# BQ_Chip.net
KiCad netlist of a schematic drawn in Altium Designer
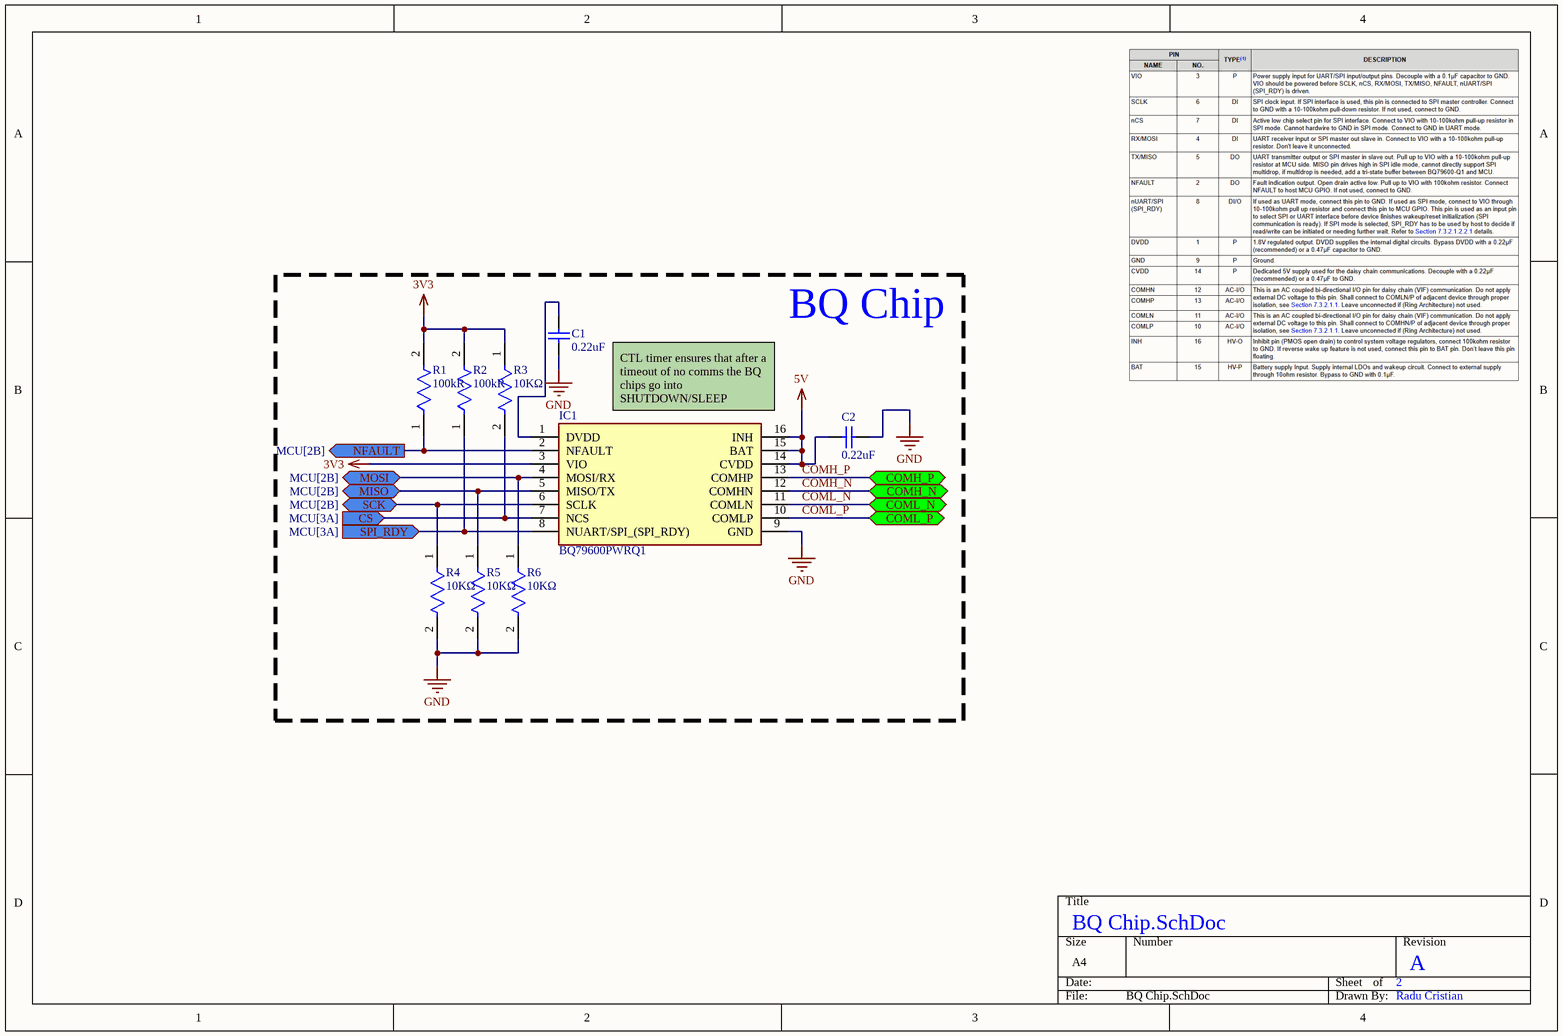
[diagram p0: BQ Chip.SchDoc]

(export (version "E")
  (design (tool "Eeschema 10.0.6"))
  (components
    (comp (ref "C1")
      (value "VJ0603Y224KXXCW1BC")
      (footprint "CAPC1608X95X40ML15T15")
      (fields (field (name "MANUFACTURER") "Vitramon") (field (name "PARAMETER 1") "0.22uF"))
      (libsource (lib "Altium Content Vault") (part "CAP"))
    )
    (comp (ref "C2")
      (value "VJ0603Y224KXXCW1BC")
      (footprint "CAPC1608X95X40ML15T15")
      (fields (field (name "MANUFACTURER") "Vitramon") (field (name "PARAMETER 1") "0.22uF"))
      (libsource (lib "Altium Content Vault") (part "CAP"))
    )
    (comp (ref "IC1")
      (value "BQ79600PWRQ1")
      (footprint "SamacSys:SOP65P640X120-16N")
      (description "Integrated Circuit")
      (fields (field (name "MOUSER PART NUMBER") "595-BQ79600PWRQ1"))
      (libsource (lib "*") (part "BQ79600PWRQ1"))
    )
    (comp (ref "R1")
      (value "MCT0603MC1003FP500")
      (footprint "FP-MCT0603-IPC_C")
      (description "RES SMD 100 OHM 1% 1/8W 0603")
      (fields (field (name "TOLERANCE") "1%") (field (name "RESISTANCE") "100kR"))
      (libsource (lib "Altium Content Vault") (part "1029c3af85768c4190bb7ad29bc67b5"))
    )
    (comp (ref "R2")
      (value "MCT0603MC1003FP500")
      (footprint "FP-MCT0603-IPC_C")
      (description "RES SMD 100 OHM 1% 1/8W 0603")
      (fields (field (name "TOLERANCE") "1%") (field (name "RESISTANCE") "100kR"))
      (libsource (lib "Altium Content Vault") (part "1029c3af85768c4190bb7ad29bc67b5"))
    )
    (comp (ref "R3")
      (value "CRGP0603F10K")
      (footprint "FP-CRGP0603-IPC_C")
      (description "CRGP 0603 10K 1%")
      (fields
        (field (name "OCTOPART") "https://octopart.com/crgp0603f10k-te+connectivity-91018721")
        (field (name "TOLERANCE") "0.01")
        (field (name "RESISTANCE") "10KΩ")
      )
      (libsource (lib "Altium Content Vault") (part "1029c3af85768c4190bb7ad29bc67b5"))
    )
    (comp (ref "R4")
      (value "CRGP0603F10K")
      (footprint "FP-CRGP0603-IPC_C")
      (description "CRGP 0603 10K 1%")
      (fields
        (field (name "OCTOPART") "https://octopart.com/crgp0603f10k-te+connectivity-91018721")
        (field (name "TOLERANCE") "0.01")
        (field (name "RESISTANCE") "10KΩ")
      )
      (libsource (lib "Altium Content Vault") (part "1029c3af85768c4190bb7ad29bc67b5"))
    )
    (comp (ref "R5")
      (value "CRGP0603F10K")
      (footprint "FP-CRGP0603-IPC_C")
      (description "CRGP 0603 10K 1%")
      (fields
        (field (name "OCTOPART") "https://octopart.com/crgp0603f10k-te+connectivity-91018721")
        (field (name "TOLERANCE") "0.01")
        (field (name "RESISTANCE") "10KΩ")
      )
      (libsource (lib "Altium Content Vault") (part "1029c3af85768c4190bb7ad29bc67b5"))
    )
    (comp (ref "R6")
      (value "CRGP0603F10K")
      (footprint "FP-CRGP0603-IPC_C")
      (description "CRGP 0603 10K 1%")
      (fields
        (field (name "OCTOPART") "https://octopart.com/crgp0603f10k-te+connectivity-91018721")
        (field (name "TOLERANCE") "0.01")
        (field (name "RESISTANCE") "10KΩ")
      )
      (libsource (lib "Altium Content Vault") (part "1029c3af85768c4190bb7ad29bc67b5"))
    )
  )
  (nets
    (net (code "1") (name "/COMH_N") (class "Default")
      (node (ref "IC1") (pin "12") (pinfunction "COMHN_12") (pintype "passive"))
    )
    (net (code "2") (name "/COMH_P") (class "Default")
      (node (ref "IC1") (pin "13") (pinfunction "COMHP_13") (pintype "passive"))
    )
    (net (code "3") (name "/COML_N") (class "Default")
      (node (ref "IC1") (pin "11") (pinfunction "COMLN_11") (pintype "passive"))
    )
    (net (code "4") (name "/COML_P") (class "Default")
      (node (ref "IC1") (pin "10") (pinfunction "COMLP_10") (pintype "passive"))
    )
    (net (code "5") (name "/CS") (class "Default")
      (node (ref "IC1") (pin "7") (pinfunction "NCS_7") (pintype "passive"))
      (node (ref "R3") (pin "2") (pinfunction "2_2") (pintype "passive"))
    )
    (net (code "6") (name "/MISO") (class "Default")
      (node (ref "IC1") (pin "5") (pinfunction "MISO/TX_5") (pintype "passive"))
      (node (ref "R5") (pin "1") (pinfunction "1_1") (pintype "passive"))
    )
    (net (code "7") (name "/MOSI") (class "Default")
      (node (ref "IC1") (pin "4") (pinfunction "MOSI/RX_4") (pintype "passive"))
      (node (ref "R6") (pin "1") (pinfunction "1_1") (pintype "passive"))
    )
    (net (code "8") (name "/NFAULT") (class "Default")
      (node (ref "IC1") (pin "2") (pinfunction "NFAULT_2") (pintype "passive"))
      (node (ref "R1") (pin "1") (pinfunction "1_1") (pintype "passive"))
    )
    (net (code "9") (name "/SCK") (class "Default")
      (node (ref "IC1") (pin "6") (pinfunction "SCLK_6") (pintype "passive"))
      (node (ref "R4") (pin "1") (pinfunction "1_1") (pintype "passive"))
    )
    (net (code "10") (name "/SPI_RDY") (class "Default")
      (node (ref "IC1") (pin "8") (pinfunction "NUART/SPI_(SPI_RDY)_8") (pintype "passive"))
      (node (ref "R2") (pin "1") (pinfunction "1_1") (pintype "passive"))
    )
    (net (code "11") (name "3V3") (class "Default")
      (node (ref "IC1") (pin "3") (pinfunction "VIO_3") (pintype "passive"))
      (node (ref "R1") (pin "2") (pinfunction "2_2") (pintype "passive"))
      (node (ref "R2") (pin "2") (pinfunction "2_2") (pintype "passive"))
      (node (ref "R3") (pin "1") (pinfunction "1_1") (pintype "passive"))
    )
    (net (code "12") (name "5V") (class "Default")
      (node (ref "C2") (pin "2") (pinfunction "2_2") (pintype "passive"))
      (node (ref "IC1") (pin "14") (pinfunction "CVDD_14") (pintype "passive"))
      (node (ref "IC1") (pin "15") (pinfunction "BAT_15") (pintype "passive"))
      (node (ref "IC1") (pin "16") (pinfunction "INH_16") (pintype "passive"))
    )
    (net (code "13") (name "GND") (class "Default")
      (node (ref "C1") (pin "2") (pinfunction "2_2") (pintype "passive"))
      (node (ref "C2") (pin "1") (pinfunction "1_1") (pintype "passive"))
      (node (ref "IC1") (pin "9") (pinfunction "GND_9") (pintype "passive"))
      (node (ref "R4") (pin "2") (pinfunction "2_2") (pintype "passive"))
      (node (ref "R5") (pin "2") (pinfunction "2_2") (pintype "passive"))
      (node (ref "R6") (pin "2") (pinfunction "2_2") (pintype "passive"))
    )
    (net (code "14") (name "Net-(IC1-DVDD)") (class "Default")
      (node (ref "C1") (pin "1") (pinfunction "1_1") (pintype "passive"))
      (node (ref "IC1") (pin "1") (pinfunction "DVDD_1") (pintype "passive"))
    )
  )
)
